# Communication.net
KiCad netlist of a schematic drawn in Altium Designer
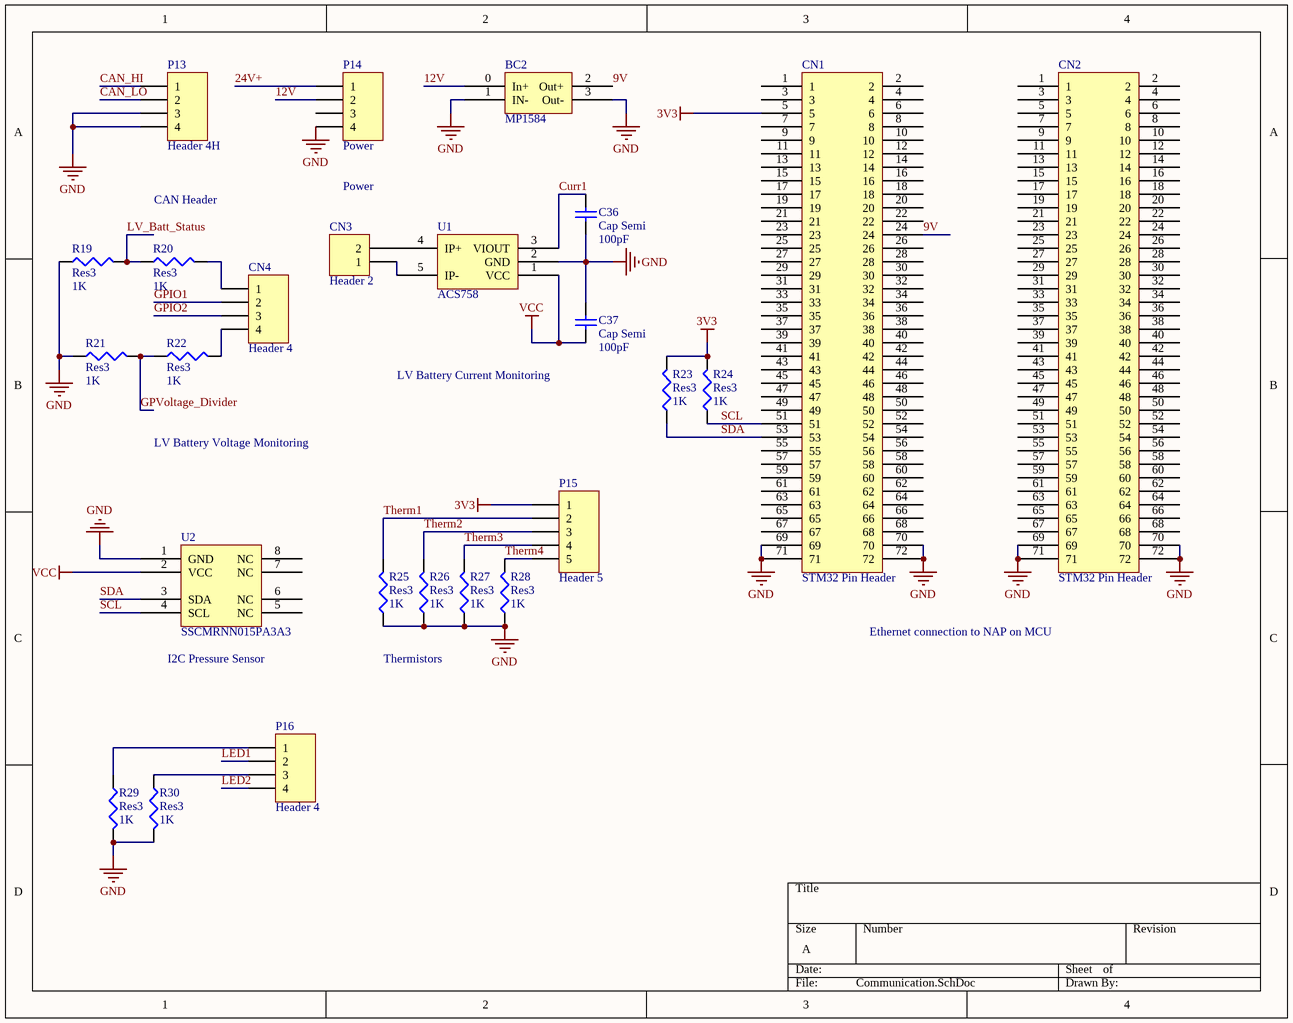
[diagram p0: Communication.SchDoc]

(export (version "E")
  (design (tool "Eeschema 10.0.6"))
  (components
    (comp (ref "BC2") (value "MP1584") (libsource (lib "Pod3") (part "MP1584")))
    (comp (ref "C36")
      (value "Cap Semi")
      (footprint "C1206")
      (description "Capacitor (Semiconductor SIM Model)")
      (fields (field (name "ALTIUM_VALUE") "100pF") (field (name "PUBLISHER") "Altium Limited"))
      (libsource (lib "Miscellaneous Devices") (part "Cap Semi"))
    )
    (comp (ref "C37")
      (value "Cap Semi")
      (footprint "C1206")
      (description "Capacitor (Semiconductor SIM Model)")
      (fields (field (name "ALTIUM_VALUE") "100pF") (field (name "PUBLISHER") "Altium Limited"))
      (libsource (lib "Miscellaneous Devices") (part "Cap Semi"))
    )
    (comp (ref "CN1") (value "STM32 Pin Header") (libsource (lib "Pod3") (part "STM32 Pin Header")))
    (comp (ref "CN2") (value "STM32 Pin Header") (libsource (lib "Pod3") (part "STM32 Pin Header")))
    (comp (ref "CN3")
      (value "Header 2")
      (footprint "HDR1X2")
      (description "Header, 2-Pin")
      (fields (field (name "PUBLISHER") "Altium Limited"))
      (libsource (lib "Miscellaneous Connectors") (part "Header 2"))
    )
    (comp (ref "CN4")
      (value "Header 4")
      (footprint "HDR1X4")
      (description "Header, 4-Pin")
      (fields (field (name "PUBLISHER") "Altium Limited"))
      (libsource (lib "Miscellaneous Connectors") (part "Header 4"))
    )
    (comp (ref "P13")
      (value "Header 4H")
      (footprint "HDR1X4H")
      (description "Header, 4-Pin, Right Angle")
      (fields (field (name "PUBLISHER") "Altium Limited"))
      (libsource (lib "Miscellaneous Connectors") (part "Header 4H"))
    )
    (comp (ref "P14")
      (value "Power")
      (footprint "HDR1X4")
      (description "Header, 4-Pin")
      (fields (field (name "PUBLISHER") "Altium Limited"))
      (libsource (lib "Miscellaneous Connectors") (part "Header 4"))
    )
    (comp (ref "P15")
      (value "Header 5")
      (footprint "HDR1X5")
      (description "Header, 5-Pin")
      (fields (field (name "PUBLISHER") "Altium Limited"))
      (libsource (lib "Miscellaneous Connectors") (part "Header 5"))
    )
    (comp (ref "P16")
      (value "Header 4")
      (footprint "HDR1X4")
      (description "Header, 4-Pin")
      (fields (field (name "PUBLISHER") "Altium Limited"))
      (libsource (lib "Miscellaneous Connectors") (part "Header 4"))
    )
    (comp (ref "R19")
      (value "Res3")
      (footprint "J1-0603")
      (description "Resistor")
      (fields (field (name "ALTIUM_VALUE") "1K") (field (name "PUBLISHER") "Altium Limited"))
      (libsource (lib "Miscellaneous Devices") (part "Res3"))
    )
    (comp (ref "R20")
      (value "Res3")
      (footprint "J1-0603")
      (description "Resistor")
      (fields (field (name "ALTIUM_VALUE") "1K") (field (name "PUBLISHER") "Altium Limited"))
      (libsource (lib "Miscellaneous Devices") (part "Res3"))
    )
    (comp (ref "R21")
      (value "Res3")
      (footprint "J1-0603")
      (description "Resistor")
      (fields (field (name "ALTIUM_VALUE") "1K") (field (name "PUBLISHER") "Altium Limited"))
      (libsource (lib "Miscellaneous Devices") (part "Res3"))
    )
    (comp (ref "R22")
      (value "Res3")
      (footprint "J1-0603")
      (description "Resistor")
      (fields (field (name "ALTIUM_VALUE") "1K") (field (name "PUBLISHER") "Altium Limited"))
      (libsource (lib "Miscellaneous Devices") (part "Res3"))
    )
    (comp (ref "R23")
      (value "Res3")
      (footprint "J1-0603")
      (description "Resistor")
      (fields (field (name "ALTIUM_VALUE") "1K") (field (name "PUBLISHER") "Altium Limited"))
      (libsource (lib "Miscellaneous Devices") (part "Res3"))
    )
    (comp (ref "R24")
      (value "Res3")
      (footprint "J1-0603")
      (description "Resistor")
      (fields (field (name "ALTIUM_VALUE") "1K") (field (name "PUBLISHER") "Altium Limited"))
      (libsource (lib "Miscellaneous Devices") (part "Res3"))
    )
    (comp (ref "R25")
      (value "Res3")
      (footprint "J1-0603")
      (description "Resistor")
      (fields (field (name "ALTIUM_VALUE") "1K") (field (name "PUBLISHER") "Altium Limited"))
      (libsource (lib "Miscellaneous Devices") (part "Res3"))
    )
    (comp (ref "R26")
      (value "Res3")
      (footprint "J1-0603")
      (description "Resistor")
      (fields (field (name "ALTIUM_VALUE") "1K") (field (name "PUBLISHER") "Altium Limited"))
      (libsource (lib "Miscellaneous Devices") (part "Res3"))
    )
    (comp (ref "R27")
      (value "Res3")
      (footprint "J1-0603")
      (description "Resistor")
      (fields (field (name "ALTIUM_VALUE") "1K") (field (name "PUBLISHER") "Altium Limited"))
      (libsource (lib "Miscellaneous Devices") (part "Res3"))
    )
    (comp (ref "R28")
      (value "Res3")
      (footprint "J1-0603")
      (description "Resistor")
      (fields (field (name "ALTIUM_VALUE") "1K") (field (name "PUBLISHER") "Altium Limited"))
      (libsource (lib "Miscellaneous Devices") (part "Res3"))
    )
    (comp (ref "R29")
      (value "Res3")
      (footprint "J1-0603")
      (description "Resistor")
      (fields (field (name "ALTIUM_VALUE") "1K") (field (name "PUBLISHER") "Altium Limited"))
      (libsource (lib "Miscellaneous Devices") (part "Res3"))
    )
    (comp (ref "R30")
      (value "Res3")
      (footprint "J1-0603")
      (description "Resistor")
      (fields (field (name "ALTIUM_VALUE") "1K") (field (name "PUBLISHER") "Altium Limited"))
      (libsource (lib "Miscellaneous Devices") (part "Res3"))
    )
    (comp (ref "U1") (value "ACS758") (footprint "ACS758") (libsource (lib "Pod2") (part "CurrSens")))
    (comp (ref "U2")
      (value "SSCMRNN015PA3A3")
      (footprint "Honeywell SMD")
      (libsource (lib "Pod2") (part "AmbPressTemp"))
    )
  )
  (nets
    (net (code "1") (name "/9V") (class "Default")
      (node (ref "BC2") (pin "2") (pinfunction "Out+_2") (pintype "passive"))
      (node (ref "CN1") (pin "24") (pinfunction "24_24") (pintype "passive"))
    )
    (net (code "2") (name "/12V") (class "Default")
      (node (ref "BC2") (pin "0") (pinfunction "In+_0") (pintype "passive"))
      (node (ref "P14") (pin "2") (pinfunction "2_2") (pintype "passive"))
    )
    (net (code "3") (name "/24V+") (class "Default")
      (node (ref "P14") (pin "1") (pinfunction "1_1") (pintype "passive"))
    )
    (net (code "4") (name "/CAN_HI") (class "Default")
      (node (ref "P13") (pin "1") (pinfunction "1_1") (pintype "passive"))
    )
    (net (code "5") (name "/CAN_LO") (class "Default")
      (node (ref "P13") (pin "2") (pinfunction "2_2") (pintype "passive"))
    )
    (net (code "6") (name "/Curr1") (class "Default")
      (node (ref "C36") (pin "2") (pinfunction "2_2") (pintype "passive"))
      (node (ref "U1") (pin "3") (pinfunction "VIOUT_3") (pintype "passive"))
    )
    (net (code "7") (name "/GPIO1") (class "Default")
      (node (ref "CN4") (pin "2") (pinfunction "2_2") (pintype "passive"))
    )
    (net (code "8") (name "/GPIO2") (class "Default")
      (node (ref "CN4") (pin "3") (pinfunction "3_3") (pintype "passive"))
    )
    (net (code "9") (name "/GPVoltage_Divider") (class "Default")
      (node (ref "R21") (pin "2") (pinfunction "2_2") (pintype "passive"))
      (node (ref "R22") (pin "1") (pinfunction "1_1") (pintype "passive"))
    )
    (net (code "10") (name "/LED1") (class "Default")
      (node (ref "P16") (pin "2") (pinfunction "2_2") (pintype "passive"))
    )
    (net (code "11") (name "/LED2") (class "Default")
      (node (ref "P16") (pin "4") (pinfunction "4_4") (pintype "passive"))
    )
    (net (code "12") (name "/LV_Batt_Status") (class "Default")
      (node (ref "R19") (pin "2") (pinfunction "2_2") (pintype "passive"))
      (node (ref "R20") (pin "1") (pinfunction "1_1") (pintype "passive"))
    )
    (net (code "13") (name "/SCL") (class "Default")
      (node (ref "CN1") (pin "51") (pinfunction "51_51") (pintype "passive"))
      (node (ref "R24") (pin "1") (pinfunction "1_1") (pintype "passive"))
      (node (ref "U2") (pin "4") (pinfunction "SCL_4") (pintype "passive"))
    )
    (net (code "14") (name "/SDA") (class "Default")
      (node (ref "CN1") (pin "53") (pinfunction "53_53") (pintype "passive"))
      (node (ref "R23") (pin "1") (pinfunction "1_1") (pintype "passive"))
      (node (ref "U2") (pin "3") (pinfunction "SDA_3") (pintype "passive"))
    )
    (net (code "15") (name "/Therm1") (class "Default")
      (node (ref "P15") (pin "2") (pinfunction "2_2") (pintype "passive"))
      (node (ref "R25") (pin "2") (pinfunction "2_2") (pintype "passive"))
    )
    (net (code "16") (name "/Therm2") (class "Default")
      (node (ref "P15") (pin "3") (pinfunction "3_3") (pintype "passive"))
      (node (ref "R26") (pin "2") (pinfunction "2_2") (pintype "passive"))
    )
    (net (code "17") (name "/Therm3") (class "Default")
      (node (ref "P15") (pin "4") (pinfunction "4_4") (pintype "passive"))
      (node (ref "R27") (pin "2") (pinfunction "2_2") (pintype "passive"))
    )
    (net (code "18") (name "/Therm4") (class "Default")
      (node (ref "P15") (pin "5") (pinfunction "5_5") (pintype "passive"))
      (node (ref "R28") (pin "2") (pinfunction "2_2") (pintype "passive"))
    )
    (net (code "19") (name "3V3") (class "Default")
      (node (ref "CN1") (pin "5") (pinfunction "5_5") (pintype "passive"))
      (node (ref "P15") (pin "1") (pinfunction "1_1") (pintype "passive"))
      (node (ref "R23") (pin "2") (pinfunction "2_2") (pintype "passive"))
      (node (ref "R24") (pin "2") (pinfunction "2_2") (pintype "passive"))
    )
    (net (code "20") (name "GND") (class "Default")
      (node (ref "BC2") (pin "1") (pinfunction "IN-_1") (pintype "passive"))
      (node (ref "BC2") (pin "3") (pinfunction "Out-_3") (pintype "passive"))
      (node (ref "C36") (pin "1") (pinfunction "1_1") (pintype "passive"))
      (node (ref "C37") (pin "2") (pinfunction "2_2") (pintype "passive"))
      (node (ref "CN1") (pin "69") (pinfunction "69_69") (pintype "passive"))
      (node (ref "CN1") (pin "70") (pinfunction "70_70") (pintype "passive"))
      (node (ref "CN1") (pin "71") (pinfunction "71_71") (pintype "passive"))
      (node (ref "CN1") (pin "72") (pinfunction "72_72") (pintype "passive"))
      (node (ref "CN2") (pin "69") (pinfunction "69_69") (pintype "passive"))
      (node (ref "CN2") (pin "70") (pinfunction "70_70") (pintype "passive"))
      (node (ref "CN2") (pin "71") (pinfunction "71_71") (pintype "passive"))
      (node (ref "CN2") (pin "72") (pinfunction "72_72") (pintype "passive"))
      (node (ref "P13") (pin "3") (pinfunction "3_3") (pintype "passive"))
      (node (ref "P13") (pin "4") (pinfunction "4_4") (pintype "passive"))
      (node (ref "P14") (pin "4") (pinfunction "4_4") (pintype "passive"))
      (node (ref "R19") (pin "1") (pinfunction "1_1") (pintype "passive"))
      (node (ref "R21") (pin "1") (pinfunction "1_1") (pintype "passive"))
      (node (ref "R25") (pin "1") (pinfunction "1_1") (pintype "passive"))
      (node (ref "R26") (pin "1") (pinfunction "1_1") (pintype "passive"))
      (node (ref "R27") (pin "1") (pinfunction "1_1") (pintype "passive"))
      (node (ref "R28") (pin "1") (pinfunction "1_1") (pintype "passive"))
      (node (ref "R29") (pin "2") (pinfunction "2_2") (pintype "passive"))
      (node (ref "R30") (pin "2") (pinfunction "2_2") (pintype "passive"))
      (node (ref "U1") (pin "2") (pinfunction "GND_2") (pintype "passive"))
      (node (ref "U2") (pin "1") (pinfunction "GND_1") (pintype "passive"))
    )
    (net (code "21") (name "Net-(CN4-Pad1)") (class "Default")
      (node (ref "CN4") (pin "1") (pinfunction "1_1") (pintype "passive"))
      (node (ref "R20") (pin "2") (pinfunction "2_2") (pintype "passive"))
    )
    (net (code "22") (name "Net-(CN4-Pad4)") (class "Default")
      (node (ref "CN4") (pin "4") (pinfunction "4_4") (pintype "passive"))
      (node (ref "R22") (pin "2") (pinfunction "2_2") (pintype "passive"))
    )
    (net (code "23") (name "Net-(P16-Pad1)") (class "Default")
      (node (ref "P16") (pin "1") (pinfunction "1_1") (pintype "passive"))
      (node (ref "R29") (pin "1") (pinfunction "1_1") (pintype "passive"))
    )
    (net (code "24") (name "Net-(P16-Pad3)") (class "Default")
      (node (ref "P16") (pin "3") (pinfunction "3_3") (pintype "passive"))
      (node (ref "R30") (pin "1") (pinfunction "1_1") (pintype "passive"))
    )
    (net (code "25") (name "Net-(U1-IP+)") (class "Default")
      (node (ref "CN3") (pin "2") (pinfunction "2_2") (pintype "passive"))
      (node (ref "U1") (pin "4") (pinfunction "IP+_4") (pintype "passive"))
    )
    (net (code "26") (name "Net-(U1-IP-)") (class "Default")
      (node (ref "CN3") (pin "1") (pinfunction "1_1") (pintype "passive"))
      (node (ref "U1") (pin "5") (pinfunction "IP-_5") (pintype "passive"))
    )
    (net (code "27") (name "VCC") (class "Default")
      (node (ref "C37") (pin "1") (pinfunction "1_1") (pintype "passive"))
      (node (ref "U1") (pin "1") (pinfunction "VCC_1") (pintype "passive"))
      (node (ref "U2") (pin "2") (pinfunction "VCC_2") (pintype "passive"))
    )
    (net (code "28") (name "unconnected-(CN1-Pad1)") (class "Default")
      (node (ref "CN1") (pin "1") (pinfunction "1_1") (pintype "passive"))
    )
    (net (code "29") (name "unconnected-(CN1-Pad2)") (class "Default")
      (node (ref "CN1") (pin "2") (pinfunction "2_2") (pintype "passive"))
    )
    (net (code "30") (name "unconnected-(CN1-Pad3)") (class "Default")
      (node (ref "CN1") (pin "3") (pinfunction "3_3") (pintype "passive"))
    )
    (net (code "31") (name "unconnected-(CN1-Pad4)") (class "Default")
      (node (ref "CN1") (pin "4") (pinfunction "4_4") (pintype "passive"))
    )
    (net (code "32") (name "unconnected-(CN1-Pad6)") (class "Default")
      (node (ref "CN1") (pin "6") (pinfunction "6_6") (pintype "passive"))
    )
    (net (code "33") (name "unconnected-(CN1-Pad7)") (class "Default")
      (node (ref "CN1") (pin "7") (pinfunction "7_7") (pintype "passive"))
    )
    (net (code "34") (name "unconnected-(CN1-Pad8)") (class "Default")
      (node (ref "CN1") (pin "8") (pinfunction "8_8") (pintype "passive"))
    )
    (net (code "35") (name "unconnected-(CN1-Pad9)") (class "Default")
      (node (ref "CN1") (pin "9") (pinfunction "9_9") (pintype "passive"))
    )
    (net (code "36") (name "unconnected-(CN1-Pad10)") (class "Default")
      (node (ref "CN1") (pin "10") (pinfunction "10_10") (pintype "passive"))
    )
    (net (code "37") (name "unconnected-(CN1-Pad11)") (class "Default")
      (node (ref "CN1") (pin "11") (pinfunction "11_11") (pintype "passive"))
    )
    (net (code "38") (name "unconnected-(CN1-Pad12)") (class "Default")
      (node (ref "CN1") (pin "12") (pinfunction "12_12") (pintype "passive"))
    )
    (net (code "39") (name "unconnected-(CN1-Pad13)") (class "Default")
      (node (ref "CN1") (pin "13") (pinfunction "13_13") (pintype "passive"))
    )
    (net (code "40") (name "unconnected-(CN1-Pad14)") (class "Default")
      (node (ref "CN1") (pin "14") (pinfunction "14_14") (pintype "passive"))
    )
    (net (code "41") (name "unconnected-(CN1-Pad15)") (class "Default")
      (node (ref "CN1") (pin "15") (pinfunction "15_15") (pintype "passive"))
    )
    (net (code "42") (name "unconnected-(CN1-Pad16)") (class "Default")
      (node (ref "CN1") (pin "16") (pinfunction "16_16") (pintype "passive"))
    )
    (net (code "43") (name "unconnected-(CN1-Pad17)") (class "Default")
      (node (ref "CN1") (pin "17") (pinfunction "17_17") (pintype "passive"))
    )
    (net (code "44") (name "unconnected-(CN1-Pad18)") (class "Default")
      (node (ref "CN1") (pin "18") (pinfunction "18_18") (pintype "passive"))
    )
    (net (code "45") (name "unconnected-(CN1-Pad19)") (class "Default")
      (node (ref "CN1") (pin "19") (pinfunction "19_19") (pintype "passive"))
    )
    (net (code "46") (name "unconnected-(CN1-Pad20)") (class "Default")
      (node (ref "CN1") (pin "20") (pinfunction "20_20") (pintype "passive"))
    )
    (net (code "47") (name "unconnected-(CN1-Pad21)") (class "Default")
      (node (ref "CN1") (pin "21") (pinfunction "21_21") (pintype "passive"))
    )
    (net (code "48") (name "unconnected-(CN1-Pad22)") (class "Default")
      (node (ref "CN1") (pin "22") (pinfunction "22_22") (pintype "passive"))
    )
    (net (code "49") (name "unconnected-(CN1-Pad23)") (class "Default")
      (node (ref "CN1") (pin "23") (pinfunction "23_23") (pintype "passive"))
    )
    (net (code "50") (name "unconnected-(CN1-Pad25)") (class "Default")
      (node (ref "CN1") (pin "25") (pinfunction "25_25") (pintype "passive"))
    )
    (net (code "51") (name "unconnected-(CN1-Pad26)") (class "Default")
      (node (ref "CN1") (pin "26") (pinfunction "26_26") (pintype "passive"))
    )
    (net (code "52") (name "unconnected-(CN1-Pad27)") (class "Default")
      (node (ref "CN1") (pin "27") (pinfunction "27_27") (pintype "passive"))
    )
    (net (code "53") (name "unconnected-(CN1-Pad28)") (class "Default")
      (node (ref "CN1") (pin "28") (pinfunction "28_28") (pintype "passive"))
    )
    (net (code "54") (name "unconnected-(CN1-Pad29)") (class "Default")
      (node (ref "CN1") (pin "29") (pinfunction "29_29") (pintype "passive"))
    )
    (net (code "55") (name "unconnected-(CN1-Pad30)") (class "Default")
      (node (ref "CN1") (pin "30") (pinfunction "30_30") (pintype "passive"))
    )
    (net (code "56") (name "unconnected-(CN1-Pad31)") (class "Default")
      (node (ref "CN1") (pin "31") (pinfunction "31_31") (pintype "passive"))
    )
    (net (code "57") (name "unconnected-(CN1-Pad32)") (class "Default")
      (node (ref "CN1") (pin "32") (pinfunction "32_32") (pintype "passive"))
    )
    (net (code "58") (name "unconnected-(CN1-Pad33)") (class "Default")
      (node (ref "CN1") (pin "33") (pinfunction "33_33") (pintype "passive"))
    )
    (net (code "59") (name "unconnected-(CN1-Pad34)") (class "Default")
      (node (ref "CN1") (pin "34") (pinfunction "34_34") (pintype "passive"))
    )
    (net (code "60") (name "unconnected-(CN1-Pad35)") (class "Default")
      (node (ref "CN1") (pin "35") (pinfunction "35_35") (pintype "passive"))
    )
    (net (code "61") (name "unconnected-(CN1-Pad36)") (class "Default")
      (node (ref "CN1") (pin "36") (pinfunction "36_36") (pintype "passive"))
    )
    (net (code "62") (name "unconnected-(CN1-Pad37)") (class "Default")
      (node (ref "CN1") (pin "37") (pinfunction "37_37") (pintype "passive"))
    )
    (net (code "63") (name "unconnected-(CN1-Pad38)") (class "Default")
      (node (ref "CN1") (pin "38") (pinfunction "38_38") (pintype "passive"))
    )
    (net (code "64") (name "unconnected-(CN1-Pad39)") (class "Default")
      (node (ref "CN1") (pin "39") (pinfunction "39_39") (pintype "passive"))
    )
    (net (code "65") (name "unconnected-(CN1-Pad40)") (class "Default")
      (node (ref "CN1") (pin "40") (pinfunction "40_40") (pintype "passive"))
    )
    (net (code "66") (name "unconnected-(CN1-Pad41)") (class "Default")
      (node (ref "CN1") (pin "41") (pinfunction "41_41") (pintype "passive"))
    )
    (net (code "67") (name "unconnected-(CN1-Pad42)") (class "Default")
      (node (ref "CN1") (pin "42") (pinfunction "42_42") (pintype "passive"))
    )
    (net (code "68") (name "unconnected-(CN1-Pad43)") (class "Default")
      (node (ref "CN1") (pin "43") (pinfunction "43_43") (pintype "passive"))
    )
    (net (code "69") (name "unconnected-(CN1-Pad44)") (class "Default")
      (node (ref "CN1") (pin "44") (pinfunction "44_44") (pintype "passive"))
    )
    (net (code "70") (name "unconnected-(CN1-Pad45)") (class "Default")
      (node (ref "CN1") (pin "45") (pinfunction "45_45") (pintype "passive"))
    )
    (net (code "71") (name "unconnected-(CN1-Pad46)") (class "Default")
      (node (ref "CN1") (pin "46") (pinfunction "46_46") (pintype "passive"))
    )
    (net (code "72") (name "unconnected-(CN1-Pad47)") (class "Default")
      (node (ref "CN1") (pin "47") (pinfunction "47_47") (pintype "passive"))
    )
    (net (code "73") (name "unconnected-(CN1-Pad48)") (class "Default")
      (node (ref "CN1") (pin "48") (pinfunction "48_48") (pintype "passive"))
    )
    (net (code "74") (name "unconnected-(CN1-Pad49)") (class "Default")
      (node (ref "CN1") (pin "49") (pinfunction "49_49") (pintype "passive"))
    )
    (net (code "75") (name "unconnected-(CN1-Pad50)") (class "Default")
      (node (ref "CN1") (pin "50") (pinfunction "50_50") (pintype "passive"))
    )
    (net (code "76") (name "unconnected-(CN1-Pad52)") (class "Default")
      (node (ref "CN1") (pin "52") (pinfunction "52_52") (pintype "passive"))
    )
    (net (code "77") (name "unconnected-(CN1-Pad54)") (class "Default")
      (node (ref "CN1") (pin "54") (pinfunction "54_54") (pintype "passive"))
    )
    (net (code "78") (name "unconnected-(CN1-Pad55)") (class "Default")
      (node (ref "CN1") (pin "55") (pinfunction "55_55") (pintype "passive"))
    )
    (net (code "79") (name "unconnected-(CN1-Pad56)") (class "Default")
      (node (ref "CN1") (pin "56") (pinfunction "56_56") (pintype "passive"))
    )
    (net (code "80") (name "unconnected-(CN1-Pad57)") (class "Default")
      (node (ref "CN1") (pin "57") (pinfunction "57_57") (pintype "passive"))
    )
    (net (code "81") (name "unconnected-(CN1-Pad58)") (class "Default")
      (node (ref "CN1") (pin "58") (pinfunction "58_58") (pintype "passive"))
    )
    (net (code "82") (name "unconnected-(CN1-Pad59)") (class "Default")
      (node (ref "CN1") (pin "59") (pinfunction "59_59") (pintype "passive"))
    )
    (net (code "83") (name "unconnected-(CN1-Pad60)") (class "Default")
      (node (ref "CN1") (pin "60") (pinfunction "60_60") (pintype "passive"))
    )
    (net (code "84") (name "unconnected-(CN1-Pad61)") (class "Default")
      (node (ref "CN1") (pin "61") (pinfunction "61_61") (pintype "passive"))
    )
    (net (code "85") (name "unconnected-(CN1-Pad62)") (class "Default")
      (node (ref "CN1") (pin "62") (pinfunction "62_62") (pintype "passive"))
    )
    (net (code "86") (name "unconnected-(CN1-Pad63)") (class "Default")
      (node (ref "CN1") (pin "63") (pinfunction "63_63") (pintype "passive"))
    )
    (net (code "87") (name "unconnected-(CN1-Pad64)") (class "Default")
      (node (ref "CN1") (pin "64") (pinfunction "64_64") (pintype "passive"))
    )
    (net (code "88") (name "unconnected-(CN1-Pad65)") (class "Default")
      (node (ref "CN1") (pin "65") (pinfunction "65_65") (pintype "passive"))
    )
    (net (code "89") (name "unconnected-(CN1-Pad66)") (class "Default")
      (node (ref "CN1") (pin "66") (pinfunction "66_66") (pintype "passive"))
    )
    (net (code "90") (name "unconnected-(CN1-Pad67)") (class "Default")
      (node (ref "CN1") (pin "67") (pinfunction "67_67") (pintype "passive"))
    )
    (net (code "91") (name "unconnected-(CN1-Pad68)") (class "Default")
      (node (ref "CN1") (pin "68") (pinfunction "68_68") (pintype "passive"))
    )
    (net (code "92") (name "unconnected-(CN2-Pad1)") (class "Default")
      (node (ref "CN2") (pin "1") (pinfunction "1_1") (pintype "passive"))
    )
    (net (code "93") (name "unconnected-(CN2-Pad2)") (class "Default")
      (node (ref "CN2") (pin "2") (pinfunction "2_2") (pintype "passive"))
    )
    (net (code "94") (name "unconnected-(CN2-Pad3)") (class "Default")
      (node (ref "CN2") (pin "3") (pinfunction "3_3") (pintype "passive"))
    )
    (net (code "95") (name "unconnected-(CN2-Pad4)") (class "Default")
      (node (ref "CN2") (pin "4") (pinfunction "4_4") (pintype "passive"))
    )
    (net (code "96") (name "unconnected-(CN2-Pad5)") (class "Default")
      (node (ref "CN2") (pin "5") (pinfunction "5_5") (pintype "passive"))
    )
    (net (code "97") (name "unconnected-(CN2-Pad6)") (class "Default")
      (node (ref "CN2") (pin "6") (pinfunction "6_6") (pintype "passive"))
    )
    (net (code "98") (name "unconnected-(CN2-Pad7)") (class "Default")
      (node (ref "CN2") (pin "7") (pinfunction "7_7") (pintype "passive"))
    )
    (net (code "99") (name "unconnected-(CN2-Pad8)") (class "Default")
      (node (ref "CN2") (pin "8") (pinfunction "8_8") (pintype "passive"))
    )
    (net (code "100") (name "unconnected-(CN2-Pad9)") (class "Default")
      (node (ref "CN2") (pin "9") (pinfunction "9_9") (pintype "passive"))
    )
    (net (code "101") (name "unconnected-(CN2-Pad10)") (class "Default")
      (node (ref "CN2") (pin "10") (pinfunction "10_10") (pintype "passive"))
    )
    (net (code "102") (name "unconnected-(CN2-Pad11)") (class "Default")
      (node (ref "CN2") (pin "11") (pinfunction "11_11") (pintype "passive"))
    )
    (net (code "103") (name "unconnected-(CN2-Pad12)") (class "Default")
      (node (ref "CN2") (pin "12") (pinfunction "12_12") (pintype "passive"))
    )
    (net (code "104") (name "unconnected-(CN2-Pad13)") (class "Default")
      (node (ref "CN2") (pin "13") (pinfunction "13_13") (pintype "passive"))
    )
    (net (code "105") (name "unconnected-(CN2-Pad14)") (class "Default")
      (node (ref "CN2") (pin "14") (pinfunction "14_14") (pintype "passive"))
    )
    (net (code "106") (name "unconnected-(CN2-Pad15)") (class "Default")
      (node (ref "CN2") (pin "15") (pinfunction "15_15") (pintype "passive"))
    )
    (net (code "107") (name "unconnected-(CN2-Pad16)") (class "Default")
      (node (ref "CN2") (pin "16") (pinfunction "16_16") (pintype "passive"))
    )
    (net (code "108") (name "unconnected-(CN2-Pad17)") (class "Default")
      (node (ref "CN2") (pin "17") (pinfunction "17_17") (pintype "passive"))
    )
    (net (code "109") (name "unconnected-(CN2-Pad18)") (class "Default")
      (node (ref "CN2") (pin "18") (pinfunction "18_18") (pintype "passive"))
    )
    (net (code "110") (name "unconnected-(CN2-Pad19)") (class "Default")
      (node (ref "CN2") (pin "19") (pinfunction "19_19") (pintype "passive"))
    )
    (net (code "111") (name "unconnected-(CN2-Pad20)") (class "Default")
      (node (ref "CN2") (pin "20") (pinfunction "20_20") (pintype "passive"))
    )
    (net (code "112") (name "unconnected-(CN2-Pad21)") (class "Default")
      (node (ref "CN2") (pin "21") (pinfunction "21_21") (pintype "passive"))
    )
    (net (code "113") (name "unconnected-(CN2-Pad22)") (class "Default")
      (node (ref "CN2") (pin "22") (pinfunction "22_22") (pintype "passive"))
    )
    (net (code "114") (name "unconnected-(CN2-Pad23)") (class "Default")
      (node (ref "CN2") (pin "23") (pinfunction "23_23") (pintype "passive"))
    )
    (net (code "115") (name "unconnected-(CN2-Pad24)") (class "Default")
      (node (ref "CN2") (pin "24") (pinfunction "24_24") (pintype "passive"))
    )
    (net (code "116") (name "unconnected-(CN2-Pad25)") (class "Default")
      (node (ref "CN2") (pin "25") (pinfunction "25_25") (pintype "passive"))
    )
    (net (code "117") (name "unconnected-(CN2-Pad26)") (class "Default")
      (node (ref "CN2") (pin "26") (pinfunction "26_26") (pintype "passive"))
    )
    (net (code "118") (name "unconnected-(CN2-Pad27)") (class "Default")
      (node (ref "CN2") (pin "27") (pinfunction "27_27") (pintype "passive"))
    )
    (net (code "119") (name "unconnected-(CN2-Pad28)") (class "Default")
      (node (ref "CN2") (pin "28") (pinfunction "28_28") (pintype "passive"))
    )
    (net (code "120") (name "unconnected-(CN2-Pad29)") (class "Default")
      (node (ref "CN2") (pin "29") (pinfunction "29_29") (pintype "passive"))
    )
    (net (code "121") (name "unconnected-(CN2-Pad30)") (class "Default")
      (node (ref "CN2") (pin "30") (pinfunction "30_30") (pintype "passive"))
    )
    (net (code "122") (name "unconnected-(CN2-Pad31)") (class "Default")
      (node (ref "CN2") (pin "31") (pinfunction "31_31") (pintype "passive"))
    )
    (net (code "123") (name "unconnected-(CN2-Pad32)") (class "Default")
      (node (ref "CN2") (pin "32") (pinfunction "32_32") (pintype "passive"))
    )
    (net (code "124") (name "unconnected-(CN2-Pad33)") (class "Default")
      (node (ref "CN2") (pin "33") (pinfunction "33_33") (pintype "passive"))
    )
    (net (code "125") (name "unconnected-(CN2-Pad34)") (class "Default")
      (node (ref "CN2") (pin "34") (pinfunction "34_34") (pintype "passive"))
    )
    (net (code "126") (name "unconnected-(CN2-Pad35)") (class "Default")
      (node (ref "CN2") (pin "35") (pinfunction "35_35") (pintype "passive"))
    )
    (net (code "127") (name "unconnected-(CN2-Pad36)") (class "Default")
      (node (ref "CN2") (pin "36") (pinfunction "36_36") (pintype "passive"))
    )
    (net (code "128") (name "unconnected-(CN2-Pad37)") (class "Default")
      (node (ref "CN2") (pin "37") (pinfunction "37_37") (pintype "passive"))
    )
    (net (code "129") (name "unconnected-(CN2-Pad38)") (class "Default")
      (node (ref "CN2") (pin "38") (pinfunction "38_38") (pintype "passive"))
    )
    (net (code "130") (name "unconnected-(CN2-Pad39)") (class "Default")
      (node (ref "CN2") (pin "39") (pinfunction "39_39") (pintype "passive"))
    )
    (net (code "131") (name "unconnected-(CN2-Pad40)") (class "Default")
      (node (ref "CN2") (pin "40") (pinfunction "40_40") (pintype "passive"))
    )
    (net (code "132") (name "unconnected-(CN2-Pad41)") (class "Default")
      (node (ref "CN2") (pin "41") (pinfunction "41_41") (pintype "passive"))
    )
    (net (code "133") (name "unconnected-(CN2-Pad42)") (class "Default")
      (node (ref "CN2") (pin "42") (pinfunction "42_42") (pintype "passive"))
    )
    (net (code "134") (name "unconnected-(CN2-Pad43)") (class "Default")
      (node (ref "CN2") (pin "43") (pinfunction "43_43") (pintype "passive"))
    )
    (net (code "135") (name "unconnected-(CN2-Pad44)") (class "Default")
      (node (ref "CN2") (pin "44") (pinfunction "44_44") (pintype "passive"))
    )
    (net (code "136") (name "unconnected-(CN2-Pad45)") (class "Default")
      (node (ref "CN2") (pin "45") (pinfunction "45_45") (pintype "passive"))
    )
    (net (code "137") (name "unconnected-(CN2-Pad46)") (class "Default")
      (node (ref "CN2") (pin "46") (pinfunction "46_46") (pintype "passive"))
    )
    (net (code "138") (name "unconnected-(CN2-Pad47)") (class "Default")
      (node (ref "CN2") (pin "47") (pinfunction "47_47") (pintype "passive"))
    )
    (net (code "139") (name "unconnected-(CN2-Pad48)") (class "Default")
      (node (ref "CN2") (pin "48") (pinfunction "48_48") (pintype "passive"))
    )
    (net (code "140") (name "unconnected-(CN2-Pad49)") (class "Default")
      (node (ref "CN2") (pin "49") (pinfunction "49_49") (pintype "passive"))
    )
    (net (code "141") (name "unconnected-(CN2-Pad50)") (class "Default")
      (node (ref "CN2") (pin "50") (pinfunction "50_50") (pintype "passive"))
    )
    (net (code "142") (name "unconnected-(CN2-Pad51)") (class "Default")
      (node (ref "CN2") (pin "51") (pinfunction "51_51") (pintype "passive"))
    )
    (net (code "143") (name "unconnected-(CN2-Pad52)") (class "Default")
      (node (ref "CN2") (pin "52") (pinfunction "52_52") (pintype "passive"))
    )
    (net (code "144") (name "unconnected-(CN2-Pad53)") (class "Default")
      (node (ref "CN2") (pin "53") (pinfunction "53_53") (pintype "passive"))
    )
    (net (code "145") (name "unconnected-(CN2-Pad54)") (class "Default")
      (node (ref "CN2") (pin "54") (pinfunction "54_54") (pintype "passive"))
    )
    (net (code "146") (name "unconnected-(CN2-Pad55)") (class "Default")
      (node (ref "CN2") (pin "55") (pinfunction "55_55") (pintype "passive"))
    )
    (net (code "147") (name "unconnected-(CN2-Pad56)") (class "Default")
      (node (ref "CN2") (pin "56") (pinfunction "56_56") (pintype "passive"))
    )
    (net (code "148") (name "unconnected-(CN2-Pad57)") (class "Default")
      (node (ref "CN2") (pin "57") (pinfunction "57_57") (pintype "passive"))
    )
    (net (code "149") (name "unconnected-(CN2-Pad58)") (class "Default")
      (node (ref "CN2") (pin "58") (pinfunction "58_58") (pintype "passive"))
    )
    (net (code "150") (name "unconnected-(CN2-Pad59)") (class "Default")
      (node (ref "CN2") (pin "59") (pinfunction "59_59") (pintype "passive"))
    )
    (net (code "151") (name "unconnected-(CN2-Pad60)") (class "Default")
      (node (ref "CN2") (pin "60") (pinfunction "60_60") (pintype "passive"))
    )
    (net (code "152") (name "unconnected-(CN2-Pad61)") (class "Default")
      (node (ref "CN2") (pin "61") (pinfunction "61_61") (pintype "passive"))
    )
    (net (code "153") (name "unconnected-(CN2-Pad62)") (class "Default")
      (node (ref "CN2") (pin "62") (pinfunction "62_62") (pintype "passive"))
    )
    (net (code "154") (name "unconnected-(CN2-Pad63)") (class "Default")
      (node (ref "CN2") (pin "63") (pinfunction "63_63") (pintype "passive"))
    )
    (net (code "155") (name "unconnected-(CN2-Pad64)") (class "Default")
      (node (ref "CN2") (pin "64") (pinfunction "64_64") (pintype "passive"))
    )
    (net (code "156") (name "unconnected-(CN2-Pad65)") (class "Default")
      (node (ref "CN2") (pin "65") (pinfunction "65_65") (pintype "passive"))
    )
    (net (code "157") (name "unconnected-(CN2-Pad66)") (class "Default")
      (node (ref "CN2") (pin "66") (pinfunction "66_66") (pintype "passive"))
    )
    (net (code "158") (name "unconnected-(CN2-Pad67)") (class "Default")
      (node (ref "CN2") (pin "67") (pinfunction "67_67") (pintype "passive"))
    )
    (net (code "159") (name "unconnected-(CN2-Pad68)") (class "Default")
      (node (ref "CN2") (pin "68") (pinfunction "68_68") (pintype "passive"))
    )
    (net (code "160") (name "unconnected-(P14-Pad3)") (class "Default")
      (node (ref "P14") (pin "3") (pinfunction "3_3") (pintype "passive"))
    )
    (net (code "161") (name "unconnected-(U2-NC-Pad5)") (class "Default")
      (node (ref "U2") (pin "5") (pinfunction "NC_5") (pintype "passive"))
    )
    (net (code "162") (name "unconnected-(U2-NC-Pad6)") (class "Default")
      (node (ref "U2") (pin "6") (pinfunction "NC_6") (pintype "passive"))
    )
    (net (code "163") (name "unconnected-(U2-NC-Pad7)") (class "Default")
      (node (ref "U2") (pin "7") (pinfunction "NC_7") (pintype "passive"))
    )
    (net (code "164") (name "unconnected-(U2-NC-Pad8)") (class "Default")
      (node (ref "U2") (pin "8") (pinfunction "NC_8") (pintype "passive"))
    )
  )
)
